# bike-blinky.net
KiCad netlist of a schematic drawn in EAGLE
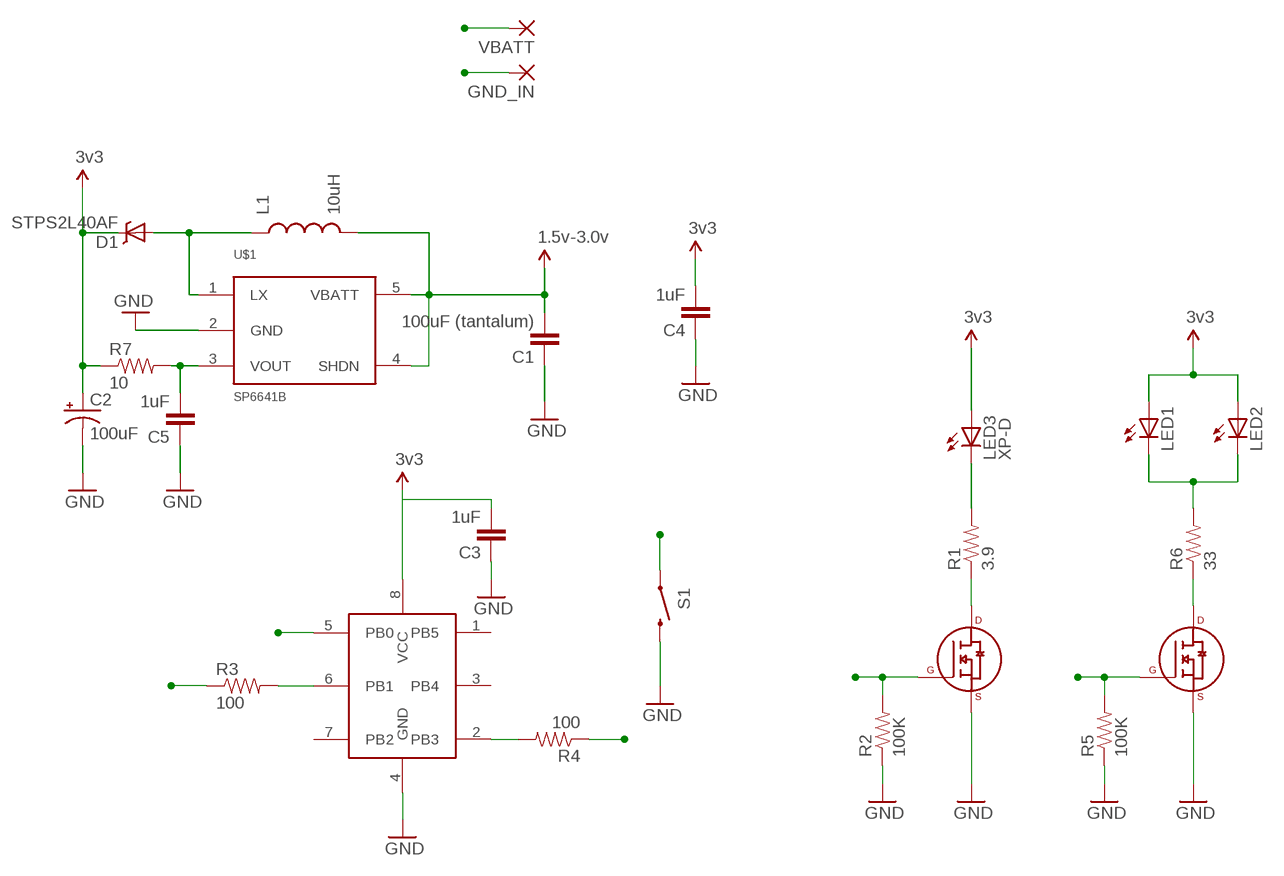
[diagram p0: schematic, sheet 1]

(export (version "E")
  (design (tool "Eeschema 10.0.6"))
  (components
    (comp (ref "C1")
      (value "100uF (tantalum)")
      (footprint "eagle-import:1206")
      (libsource (lib "eagle-import") (part "CAP1206"))
    )
    (comp (ref "C2")
      (value "100uF")
      (footprint "eagle-import:PANASONIC_C")
      (libsource (lib "eagle-import") (part "CAP_POLC"))
    )
    (comp (ref "C3")
      (value "1uF")
      (footprint "eagle-import:0603-CAP")
      (libsource (lib "eagle-import") (part "CAP0603-CAP"))
    )
    (comp (ref "C4")
      (value "1uF")
      (footprint "eagle-import:0603-CAP")
      (libsource (lib "eagle-import") (part "CAP0603-CAP"))
    )
    (comp (ref "C5")
      (value "1uF")
      (footprint "eagle-import:0603-CAP")
      (libsource (lib "eagle-import") (part "CAP0603-CAP"))
    )
    (comp (ref "D1")
      (value "STPS2L40AF")
      (footprint "eagle-import:SMA-DIODE")
      (libsource (lib "eagle-import") (part "MBRA140"))
    )
    (comp (ref "GND_IN")
      (value "WIREPAD2,54/1,0")
      (footprint "eagle-import:2,54_1,0")
      (libsource (lib "eagle-import") (part "WIREPAD2,54/1,0"))
    )
    (comp (ref "L1")
      (value "10uH")
      (footprint "eagle-import:1007")
      (libsource (lib "eagle-import") (part "INDUCTOR1007"))
    )
    (comp (ref "LED1")
      (value "LED3MM")
      (footprint "eagle-import:LED3MM")
      (libsource (lib "eagle-import") (part "LED3MM"))
    )
    (comp (ref "LED2")
      (value "LED3MM")
      (footprint "eagle-import:LED3MM")
      (libsource (lib "eagle-import") (part "LED3MM"))
    )
    (comp (ref "LED3")
      (value "XP-D")
      (footprint "eagle-import:XB-D-REV1")
      (libsource (lib "eagle-import") (part "XLAMP-XB-D-LED"))
    )
    (comp (ref "R1")
      (value "3.9")
      (footprint "eagle-import:0603-RES")
      (libsource (lib "eagle-import") (part "RESISTOR0603-RES"))
    )
    (comp (ref "R2")
      (value "100K")
      (footprint "eagle-import:0603-RES")
      (libsource (lib "eagle-import") (part "RESISTOR0603-RES"))
    )
    (comp (ref "R3")
      (value "100")
      (footprint "eagle-import:0603-RES")
      (libsource (lib "eagle-import") (part "RESISTOR0603-RES"))
    )
    (comp (ref "R4")
      (value "100")
      (footprint "eagle-import:0603-RES")
      (libsource (lib "eagle-import") (part "RESISTOR0603-RES"))
    )
    (comp (ref "R5")
      (value "100K")
      (footprint "eagle-import:0603-RES")
      (libsource (lib "eagle-import") (part "RESISTOR0603-RES"))
    )
    (comp (ref "R6")
      (value "33")
      (footprint "eagle-import:0603-RES")
      (libsource (lib "eagle-import") (part "RESISTOR0603-RES"))
    )
    (comp (ref "R7")
      (value "10")
      (footprint "eagle-import:0603-RES")
      (libsource (lib "eagle-import") (part "SparkFun-Passives_RESISTOR0603-RES"))
    )
    (comp (ref "S1")
      (value "SWITCH-MOMENTARY-2SMD-2")
      (footprint "eagle-import:TACTILE_SWITCH_SMD-2")
      (libsource (lib "eagle-import") (part "SWITCH-MOMENTARY-2SMD-2"))
    )
    (comp (ref "U$1")
      (value "SP6641B")
      (footprint "eagle-import:SOT23-5")
      (libsource (lib "eagle-import") (part "SP6641SP6641A/B"))
    )
    (comp (ref "U$2")
      (value "ATTINY13")
      (footprint "eagle-import:WSOIC-8")
      (libsource (lib "eagle-import") (part "ATTINY13"))
    )
    (comp (ref "U$7")
      (value "NDS351AN")
      (footprint "eagle-import:SOT-23-3")
      (libsource (lib "eagle-import") (part "NDS351AN"))
    )
    (comp (ref "U$8")
      (value "NDS351AN")
      (footprint "eagle-import:SOT-23-3")
      (libsource (lib "eagle-import") (part "NDS351AN"))
    )
    (comp (ref "VBATT")
      (value "WIREPAD2,54/1,0")
      (footprint "eagle-import:2,54_1,0")
      (libsource (lib "eagle-import") (part "WIREPAD2,54/1,0"))
    )
  )
  (nets
    (net (code "1") (name "/RED") (class "Default")
      (node (ref "R2") (pin "2") (pinfunction "2_2") (pintype "passive"))
      (node (ref "R3") (pin "1") (pinfunction "1_1") (pintype "passive"))
      (node (ref "U$8") (pin "1") (pinfunction "G_1") (pintype "bidirectional"))
    )
    (net (code "2") (name "/SW") (class "Default")
      (node (ref "S1") (pin "2") (pinfunction "1_2") (pintype "passive"))
      (node (ref "U$2") (pin "5") (pinfunction "PB0_5") (pintype "bidirectional"))
    )
    (net (code "3") (name "/YEL") (class "Default")
      (node (ref "R4") (pin "1") (pinfunction "1_1") (pintype "passive"))
      (node (ref "R5") (pin "2") (pinfunction "2_2") (pintype "passive"))
      (node (ref "U$7") (pin "1") (pinfunction "G_1") (pintype "bidirectional"))
    )
    (net (code "4") (name "1.5v-3.0v") (class "Default")
      (node (ref "C1") (pin "2") (pinfunction "2_2") (pintype "passive"))
      (node (ref "L1") (pin "2") (pinfunction "2_2") (pintype "passive"))
      (node (ref "U$1") (pin "4") (pinfunction "SHDN_4") (pintype "bidirectional"))
      (node (ref "U$1") (pin "5") (pinfunction "VBATT_5") (pintype "bidirectional"))
      (node (ref "VBATT") (pin "1") (pinfunction "P_1") (pintype "passive"))
    )
    (net (code "5") (name "3v3") (class "Default")
      (node (ref "C2") (pin "+") (pinfunction "+_+") (pintype "passive"))
      (node (ref "C3") (pin "2") (pinfunction "2_2") (pintype "passive"))
      (node (ref "C4") (pin "2") (pinfunction "2_2") (pintype "passive"))
      (node (ref "D1") (pin "C") (pinfunction "C_C") (pintype "passive"))
      (node (ref "LED1") (pin "A") (pinfunction "A_A") (pintype "passive"))
      (node (ref "LED2") (pin "A") (pinfunction "A_A") (pintype "passive"))
      (node (ref "LED3") (pin "A") (pinfunction "A_A") (pintype "passive"))
      (node (ref "R7") (pin "1") (pinfunction "1_1") (pintype "passive"))
      (node (ref "U$2") (pin "8") (pinfunction "VCC_8") (pintype "bidirectional"))
    )
    (net (code "6") (name "GND") (class "Default")
      (node (ref "C1") (pin "1") (pinfunction "1_1") (pintype "passive"))
      (node (ref "C2") (pin "-") (pinfunction "-_-") (pintype "passive"))
      (node (ref "C3") (pin "1") (pinfunction "1_1") (pintype "passive"))
      (node (ref "C4") (pin "1") (pinfunction "1_1") (pintype "passive"))
      (node (ref "C5") (pin "1") (pinfunction "1_1") (pintype "passive"))
      (node (ref "GND_IN") (pin "1") (pinfunction "P_1") (pintype "passive"))
      (node (ref "R2") (pin "1") (pinfunction "1_1") (pintype "passive"))
      (node (ref "R5") (pin "1") (pinfunction "1_1") (pintype "passive"))
      (node (ref "S1") (pin "1") (pinfunction "2_1") (pintype "passive"))
      (node (ref "U$1") (pin "2") (pinfunction "GND_2") (pintype "bidirectional"))
      (node (ref "U$2") (pin "4") (pinfunction "GND_4") (pintype "bidirectional"))
      (node (ref "U$7") (pin "2") (pinfunction "S_2") (pintype "bidirectional"))
      (node (ref "U$8") (pin "2") (pinfunction "S_2") (pintype "bidirectional"))
    )
    (net (code "7") (name "Net-(LED1-C)") (class "Default")
      (node (ref "LED1") (pin "K") (pinfunction "C_K") (pintype "passive"))
      (node (ref "LED2") (pin "K") (pinfunction "C_K") (pintype "passive"))
      (node (ref "R6") (pin "2") (pinfunction "2_2") (pintype "passive"))
    )
    (net (code "8") (name "Net-(LED3-PadC)") (class "Default")
      (node (ref "LED3") (pin "C") (pinfunction "C_C") (pintype "passive"))
      (node (ref "R1") (pin "2") (pinfunction "2_2") (pintype "passive"))
    )
    (net (code "9") (name "Net-(U$1-LX)") (class "Default")
      (node (ref "D1") (pin "A") (pinfunction "A_A") (pintype "passive"))
      (node (ref "L1") (pin "1") (pinfunction "1_1") (pintype "passive"))
      (node (ref "U$1") (pin "1") (pinfunction "LX_1") (pintype "bidirectional"))
    )
    (net (code "10") (name "Net-(U$1-VOUT)") (class "Default")
      (node (ref "C5") (pin "2") (pinfunction "2_2") (pintype "passive"))
      (node (ref "R7") (pin "2") (pinfunction "2_2") (pintype "passive"))
      (node (ref "U$1") (pin "3") (pinfunction "VOUT_3") (pintype "bidirectional"))
    )
    (net (code "11") (name "Net-(U$2-PB1)") (class "Default")
      (node (ref "R3") (pin "2") (pinfunction "2_2") (pintype "passive"))
      (node (ref "U$2") (pin "6") (pinfunction "PB1_6") (pintype "bidirectional"))
    )
    (net (code "12") (name "Net-(U$2-PB3)") (class "Default")
      (node (ref "R4") (pin "2") (pinfunction "2_2") (pintype "passive"))
      (node (ref "U$2") (pin "2") (pinfunction "PB3_2") (pintype "bidirectional"))
    )
    (net (code "13") (name "Net-(U$7-D)") (class "Default")
      (node (ref "R6") (pin "1") (pinfunction "1_1") (pintype "passive"))
      (node (ref "U$7") (pin "3") (pinfunction "D_3") (pintype "bidirectional"))
    )
    (net (code "14") (name "Net-(U$8-D)") (class "Default")
      (node (ref "R1") (pin "1") (pinfunction "1_1") (pintype "passive"))
      (node (ref "U$8") (pin "3") (pinfunction "D_3") (pintype "bidirectional"))
    )
    (net (code "15") (name "unconnected-(U$2-PB2-Pad7)") (class "Default")
      (node (ref "U$2") (pin "7") (pinfunction "PB2_7") (pintype "bidirectional"))
    )
    (net (code "16") (name "unconnected-(U$2-PB4-Pad3)") (class "Default")
      (node (ref "U$2") (pin "3") (pinfunction "PB4_3") (pintype "bidirectional"))
    )
    (net (code "17") (name "unconnected-(U$2-PB5-Pad1)") (class "Default")
      (node (ref "U$2") (pin "1") (pinfunction "PB5_1") (pintype "bidirectional"))
    )
  )
)
